# pcb.net
KiCad netlist of a schematic drawn in EAGLE
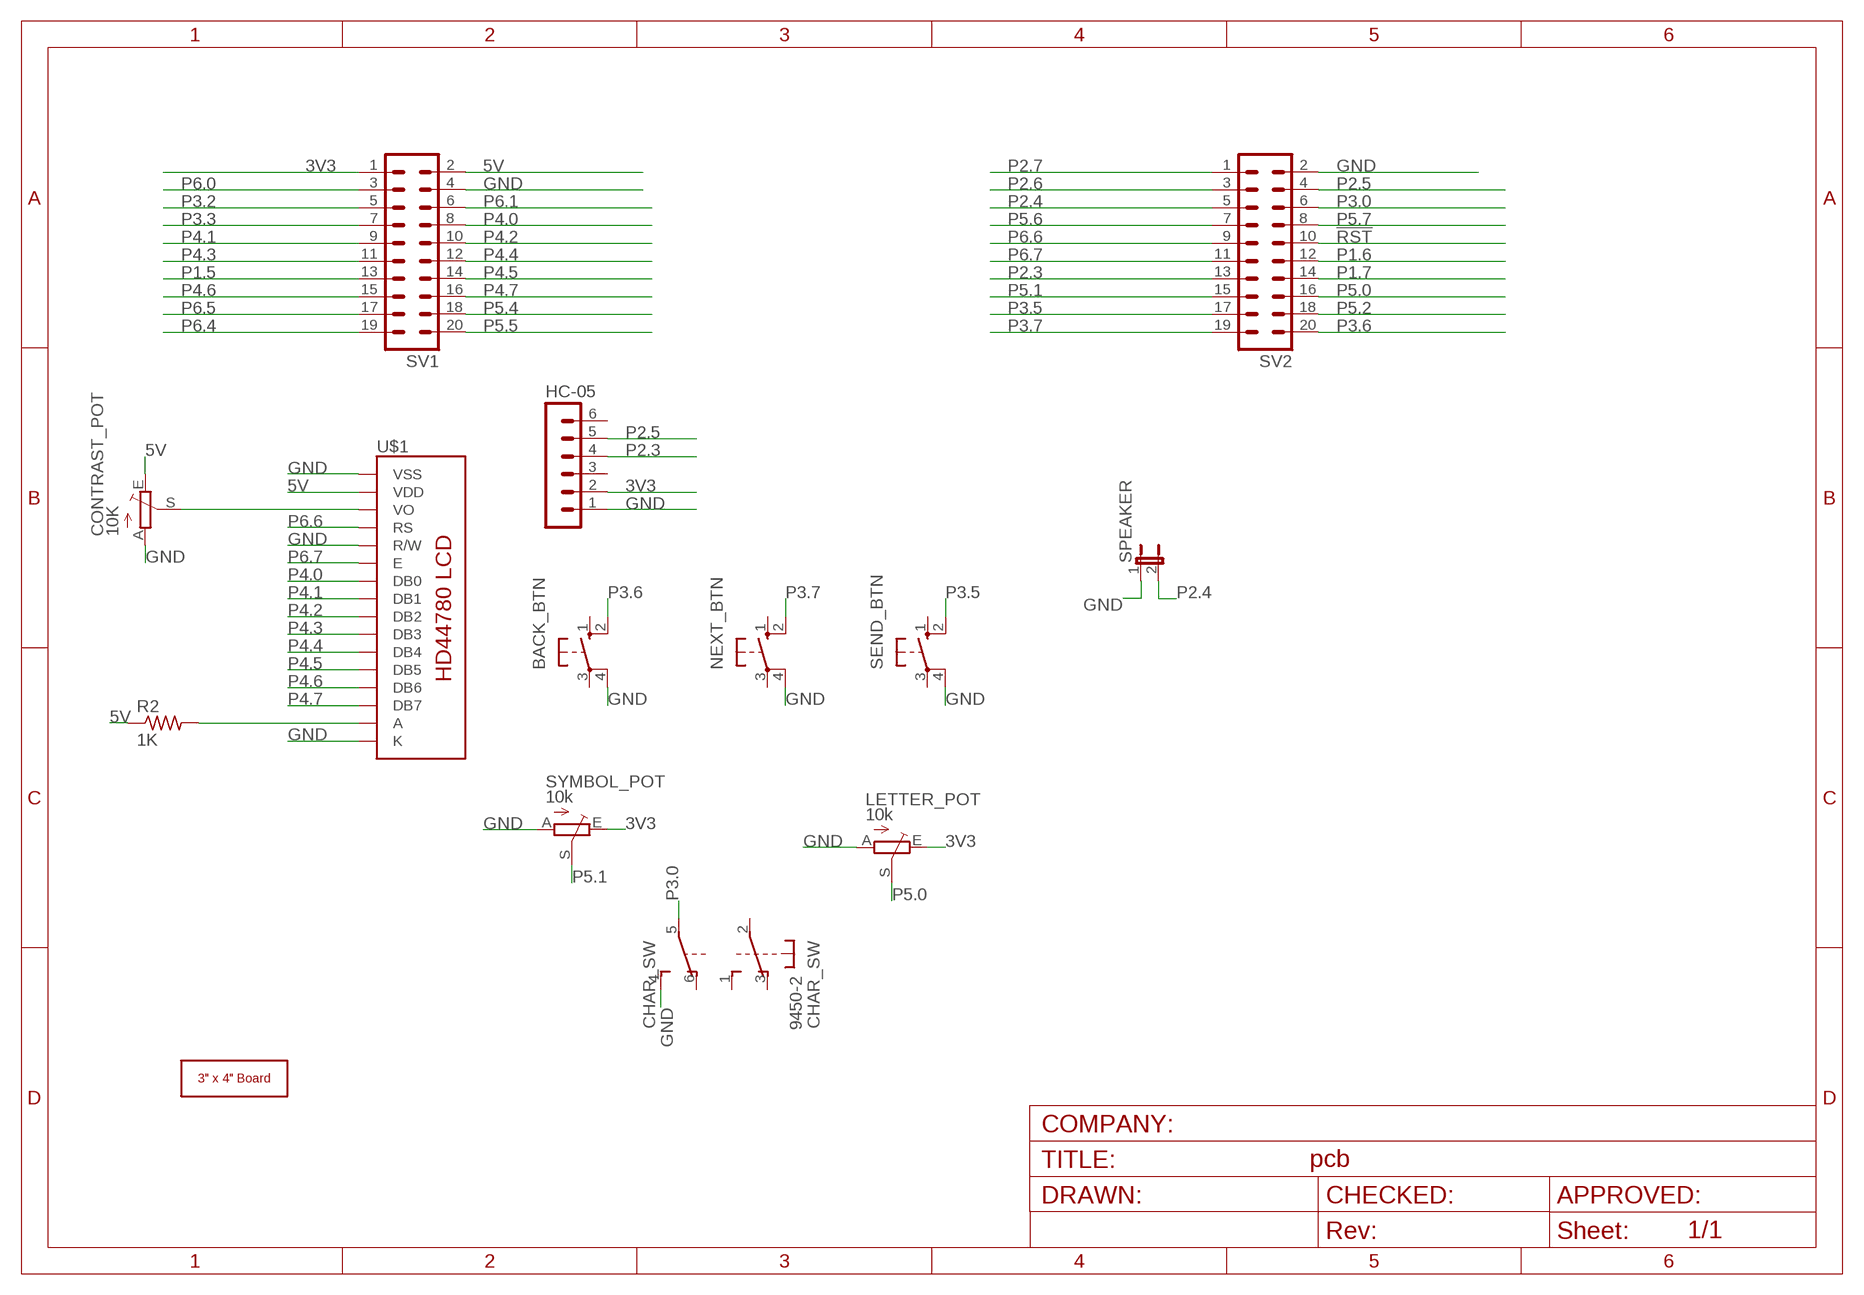
[diagram p0: schematic, sheet 1]

(export (version "E")
  (design (tool "Eeschema 10.0.6"))
  (components
    (comp (ref "BACK_BTN")
      (value "10-XX")
      (footprint "eagle-import:B3F-10XX")
      (fields (field (name "MPN") "B3F-1000"))
      (libsource (lib "eagle-import") (part "10-XX"))
    )
    (comp (ref "CHAR_SW")
      (value "9450-2")
      (footprint "eagle-import:9450-2")
      (libsource (lib "eagle-import") (part "9450-2"))
    )
    (comp (ref "CONTRAST_POT")
      (value "10K")
      (footprint "eagle-import:B25V")
      (libsource (lib "eagle-import") (part "TRIM_EU-B25V"))
    )
    (comp (ref "HC-05")
      (value "MA06-1")
      (footprint "eagle-import:MA06-1")
      (libsource (lib "eagle-import") (part "MA06-1"))
    )
    (comp (ref "LETTER_POT")
      (value "10k")
      (footprint "eagle-import:B25V")
      (libsource (lib "eagle-import") (part "TRIM_EU-B25V"))
    )
    (comp (ref "NEXT_BTN")
      (value "10-XX")
      (footprint "eagle-import:B3F-10XX")
      (fields (field (name "MPN") "B3F-1000"))
      (libsource (lib "eagle-import") (part "10-XX"))
    )
    (comp (ref "R2")
      (value "1K")
      (footprint "eagle-import:0204_7")
      (libsource (lib "eagle-import") (part "R-US_0204/7"))
    )
    (comp (ref "SEND_BTN")
      (value "10-XX")
      (footprint "eagle-import:B3F-10XX")
      (fields (field (name "MPN") "B3F-1000"))
      (libsource (lib "eagle-import") (part "10-XX"))
    )
    (comp (ref "SPEAKER")
      (value "JP1E")
      (footprint "eagle-import:JP1")
      (libsource (lib "eagle-import") (part "JP1E"))
    )
    (comp (ref "SV1")
      (value "MA10-2")
      (footprint "eagle-import:MA10-2")
      (libsource (lib "eagle-import") (part "MA10-2"))
    )
    (comp (ref "SV2")
      (value "MA10-2")
      (footprint "eagle-import:MA10-2")
      (libsource (lib "eagle-import") (part "MA10-2"))
    )
    (comp (ref "SYMBOL_POT")
      (value "10k")
      (footprint "eagle-import:B25V")
      (libsource (lib "eagle-import") (part "TRIM_EU-B25V"))
    )
    (comp (ref "U$1")
      (value "LCD-HD447804-HOLES16X2-4-HOLES")
      (footprint "eagle-import:LCD-16X2-4HOLES")
      (libsource (lib "eagle-import") (part "LCD-HD4478016X2-4-HOLES4-HOLES"))
    )
    (comp (ref "U$3")
      (value "3X4_BOARD")
      (footprint "eagle-import:3X4_BOARD_V1")
      (libsource (lib "eagle-import") (part "3X4_BOARD"))
    )
  )
  (nets
    (net (code "1") (name "/3V3") (class "Default")
      (node (ref "HC-05") (pin "2") (pinfunction "2_2") (pintype "passive"))
      (node (ref "LETTER_POT") (pin "E") (pinfunction "E_E") (pintype "passive"))
      (node (ref "SV1") (pin "1") (pinfunction "1_1") (pintype "passive"))
      (node (ref "SYMBOL_POT") (pin "E") (pinfunction "E_E") (pintype "passive"))
    )
    (net (code "2") (name "/5V") (class "Default")
      (node (ref "CONTRAST_POT") (pin "E") (pinfunction "E_E") (pintype "passive"))
      (node (ref "R2") (pin "1") (pinfunction "1_1") (pintype "passive"))
      (node (ref "SV1") (pin "2") (pinfunction "2_2") (pintype "passive"))
      (node (ref "U$1") (pin "2") (pinfunction "VDD_2") (pintype "power_in"))
    )
    (net (code "3") (name "/GND") (class "Default")
      (node (ref "BACK_BTN") (pin "4") (pinfunction "P1_4") (pintype "passive"))
      (node (ref "CHAR_SW") (pin "4") (pinfunction "S_4") (pintype "passive"))
      (node (ref "CONTRAST_POT") (pin "A") (pinfunction "A_A") (pintype "passive"))
      (node (ref "HC-05") (pin "1") (pinfunction "1_1") (pintype "passive"))
      (node (ref "LETTER_POT") (pin "A") (pinfunction "A_A") (pintype "passive"))
      (node (ref "NEXT_BTN") (pin "4") (pinfunction "P1_4") (pintype "passive"))
      (node (ref "SEND_BTN") (pin "4") (pinfunction "P1_4") (pintype "passive"))
      (node (ref "SPEAKER") (pin "1") (pinfunction "1_1") (pintype "passive"))
      (node (ref "SV1") (pin "4") (pinfunction "4_4") (pintype "passive"))
      (node (ref "SV2") (pin "2") (pinfunction "2_2") (pintype "passive"))
      (node (ref "SYMBOL_POT") (pin "A") (pinfunction "A_A") (pintype "passive"))
      (node (ref "U$1") (pin "1") (pinfunction "VSS_1") (pintype "power_in"))
      (node (ref "U$1") (pin "16") (pinfunction "K_16") (pintype "power_in"))
      (node (ref "U$1") (pin "5") (pinfunction "R/W_5") (pintype "input"))
    )
    (net (code "4") (name "/P1.5") (class "Default")
      (node (ref "SV1") (pin "13") (pinfunction "13_13") (pintype "passive"))
    )
    (net (code "5") (name "/P1.6") (class "Default")
      (node (ref "SV2") (pin "12") (pinfunction "12_12") (pintype "passive"))
    )
    (net (code "6") (name "/P1.7") (class "Default")
      (node (ref "SV2") (pin "14") (pinfunction "14_14") (pintype "passive"))
    )
    (net (code "7") (name "/P2.3") (class "Default")
      (node (ref "HC-05") (pin "4") (pinfunction "4_4") (pintype "passive"))
      (node (ref "SV2") (pin "13") (pinfunction "13_13") (pintype "passive"))
    )
    (net (code "8") (name "/P2.4") (class "Default")
      (node (ref "SPEAKER") (pin "2") (pinfunction "2_2") (pintype "passive"))
      (node (ref "SV2") (pin "5") (pinfunction "5_5") (pintype "passive"))
    )
    (net (code "9") (name "/P2.5") (class "Default")
      (node (ref "HC-05") (pin "5") (pinfunction "5_5") (pintype "passive"))
      (node (ref "SV2") (pin "4") (pinfunction "4_4") (pintype "passive"))
    )
    (net (code "10") (name "/P2.6") (class "Default")
      (node (ref "SV2") (pin "3") (pinfunction "3_3") (pintype "passive"))
    )
    (net (code "11") (name "/P2.7") (class "Default")
      (node (ref "SV2") (pin "1") (pinfunction "1_1") (pintype "passive"))
    )
    (net (code "12") (name "/P3.0") (class "Default")
      (node (ref "CHAR_SW") (pin "5") (pinfunction "P_5") (pintype "passive"))
      (node (ref "SV2") (pin "6") (pinfunction "6_6") (pintype "passive"))
    )
    (net (code "13") (name "/P3.2") (class "Default")
      (node (ref "SV1") (pin "5") (pinfunction "5_5") (pintype "passive"))
    )
    (net (code "14") (name "/P3.3") (class "Default")
      (node (ref "SV1") (pin "7") (pinfunction "7_7") (pintype "passive"))
    )
    (net (code "15") (name "/P3.5") (class "Default")
      (node (ref "SEND_BTN") (pin "2") (pinfunction "S1_2") (pintype "passive"))
      (node (ref "SV2") (pin "17") (pinfunction "17_17") (pintype "passive"))
    )
    (net (code "16") (name "/P3.6") (class "Default")
      (node (ref "BACK_BTN") (pin "2") (pinfunction "S1_2") (pintype "passive"))
      (node (ref "SV2") (pin "20") (pinfunction "20_20") (pintype "passive"))
    )
    (net (code "17") (name "/P3.7") (class "Default")
      (node (ref "NEXT_BTN") (pin "2") (pinfunction "S1_2") (pintype "passive"))
      (node (ref "SV2") (pin "19") (pinfunction "19_19") (pintype "passive"))
    )
    (net (code "18") (name "/P4.0") (class "Default")
      (node (ref "SV1") (pin "8") (pinfunction "8_8") (pintype "passive"))
      (node (ref "U$1") (pin "7") (pinfunction "DB0_7") (pintype "bidirectional"))
    )
    (net (code "19") (name "/P4.1") (class "Default")
      (node (ref "SV1") (pin "9") (pinfunction "9_9") (pintype "passive"))
      (node (ref "U$1") (pin "8") (pinfunction "DB1_8") (pintype "bidirectional"))
    )
    (net (code "20") (name "/P4.2") (class "Default")
      (node (ref "SV1") (pin "10") (pinfunction "10_10") (pintype "passive"))
      (node (ref "U$1") (pin "9") (pinfunction "DB2_9") (pintype "bidirectional"))
    )
    (net (code "21") (name "/P4.3") (class "Default")
      (node (ref "SV1") (pin "11") (pinfunction "11_11") (pintype "passive"))
      (node (ref "U$1") (pin "10") (pinfunction "DB3_10") (pintype "bidirectional"))
    )
    (net (code "22") (name "/P4.4") (class "Default")
      (node (ref "SV1") (pin "12") (pinfunction "12_12") (pintype "passive"))
      (node (ref "U$1") (pin "11") (pinfunction "DB4_11") (pintype "bidirectional"))
    )
    (net (code "23") (name "/P4.5") (class "Default")
      (node (ref "SV1") (pin "14") (pinfunction "14_14") (pintype "passive"))
      (node (ref "U$1") (pin "12") (pinfunction "DB5_12") (pintype "bidirectional"))
    )
    (net (code "24") (name "/P4.6") (class "Default")
      (node (ref "SV1") (pin "15") (pinfunction "15_15") (pintype "passive"))
      (node (ref "U$1") (pin "13") (pinfunction "DB6_13") (pintype "bidirectional"))
    )
    (net (code "25") (name "/P4.7") (class "Default")
      (node (ref "SV1") (pin "16") (pinfunction "16_16") (pintype "passive"))
      (node (ref "U$1") (pin "14") (pinfunction "DB7_14") (pintype "bidirectional"))
    )
    (net (code "26") (name "/P5.0") (class "Default")
      (node (ref "LETTER_POT") (pin "S") (pinfunction "S_S") (pintype "passive"))
      (node (ref "SV2") (pin "16") (pinfunction "16_16") (pintype "passive"))
    )
    (net (code "27") (name "/P5.1") (class "Default")
      (node (ref "SV2") (pin "15") (pinfunction "15_15") (pintype "passive"))
      (node (ref "SYMBOL_POT") (pin "S") (pinfunction "S_S") (pintype "passive"))
    )
    (net (code "28") (name "/P5.2") (class "Default")
      (node (ref "SV2") (pin "18") (pinfunction "18_18") (pintype "passive"))
    )
    (net (code "29") (name "/P5.4") (class "Default")
      (node (ref "SV1") (pin "18") (pinfunction "18_18") (pintype "passive"))
    )
    (net (code "30") (name "/P5.5") (class "Default")
      (node (ref "SV1") (pin "20") (pinfunction "20_20") (pintype "passive"))
    )
    (net (code "31") (name "/P5.6") (class "Default")
      (node (ref "SV2") (pin "7") (pinfunction "7_7") (pintype "passive"))
    )
    (net (code "32") (name "/P5.7") (class "Default")
      (node (ref "SV2") (pin "8") (pinfunction "8_8") (pintype "passive"))
    )
    (net (code "33") (name "/P6.0") (class "Default")
      (node (ref "SV1") (pin "3") (pinfunction "3_3") (pintype "passive"))
    )
    (net (code "34") (name "/P6.1") (class "Default")
      (node (ref "SV1") (pin "6") (pinfunction "6_6") (pintype "passive"))
    )
    (net (code "35") (name "/P6.4") (class "Default")
      (node (ref "SV1") (pin "19") (pinfunction "19_19") (pintype "passive"))
    )
    (net (code "36") (name "/P6.5") (class "Default")
      (node (ref "SV1") (pin "17") (pinfunction "17_17") (pintype "passive"))
    )
    (net (code "37") (name "/P6.6") (class "Default")
      (node (ref "SV2") (pin "9") (pinfunction "9_9") (pintype "passive"))
      (node (ref "U$1") (pin "4") (pinfunction "RS_4") (pintype "input"))
    )
    (net (code "38") (name "/P6.7") (class "Default")
      (node (ref "SV2") (pin "11") (pinfunction "11_11") (pintype "passive"))
      (node (ref "U$1") (pin "6") (pinfunction "E_6") (pintype "input"))
    )
    (net (code "39") (name "/~{RST}") (class "Default")
      (node (ref "SV2") (pin "10") (pinfunction "10_10") (pintype "passive"))
    )
    (net (code "40") (name "Net-(U$1-A)") (class "Default")
      (node (ref "R2") (pin "2") (pinfunction "2_2") (pintype "passive"))
      (node (ref "U$1") (pin "15") (pinfunction "A_15") (pintype "power_in"))
    )
    (net (code "41") (name "Net-(U$1-VO)") (class "Default")
      (node (ref "CONTRAST_POT") (pin "S") (pinfunction "S_S") (pintype "passive"))
      (node (ref "U$1") (pin "3") (pinfunction "VO_3") (pintype "bidirectional"))
    )
    (net (code "42") (name "unconnected-(BACK_BTN-P-Pad3)") (class "Default")
      (node (ref "BACK_BTN") (pin "3") (pinfunction "P_3") (pintype "passive"))
    )
    (net (code "43") (name "unconnected-(BACK_BTN-S-Pad1)") (class "Default")
      (node (ref "BACK_BTN") (pin "1") (pinfunction "S_1") (pintype "passive"))
    )
    (net (code "44") (name "unconnected-(CHAR_SWA-O-Pad3)") (class "Default")
      (node (ref "CHAR_SW") (pin "3") (pinfunction "O_3") (pintype "passive"))
    )
    (net (code "45") (name "unconnected-(CHAR_SWA-P-Pad2)") (class "Default")
      (node (ref "CHAR_SW") (pin "2") (pinfunction "P_2") (pintype "passive"))
    )
    (net (code "46") (name "unconnected-(CHAR_SWA-S-Pad1)") (class "Default")
      (node (ref "CHAR_SW") (pin "1") (pinfunction "S_1") (pintype "passive"))
    )
    (net (code "47") (name "unconnected-(CHAR_SWB-O-Pad6)") (class "Default")
      (node (ref "CHAR_SW") (pin "6") (pinfunction "O_6") (pintype "passive"))
    )
    (net (code "48") (name "unconnected-(HC-05-Pad3)") (class "Default")
      (node (ref "HC-05") (pin "3") (pinfunction "3_3") (pintype "passive"))
    )
    (net (code "49") (name "unconnected-(HC-05-Pad6)") (class "Default")
      (node (ref "HC-05") (pin "6") (pinfunction "6_6") (pintype "passive"))
    )
    (net (code "50") (name "unconnected-(NEXT_BTN-P-Pad3)") (class "Default")
      (node (ref "NEXT_BTN") (pin "3") (pinfunction "P_3") (pintype "passive"))
    )
    (net (code "51") (name "unconnected-(NEXT_BTN-S-Pad1)") (class "Default")
      (node (ref "NEXT_BTN") (pin "1") (pinfunction "S_1") (pintype "passive"))
    )
    (net (code "52") (name "unconnected-(SEND_BTN-P-Pad3)") (class "Default")
      (node (ref "SEND_BTN") (pin "3") (pinfunction "P_3") (pintype "passive"))
    )
    (net (code "53") (name "unconnected-(SEND_BTN-S-Pad1)") (class "Default")
      (node (ref "SEND_BTN") (pin "1") (pinfunction "S_1") (pintype "passive"))
    )
  )
)
